# LiDAR_Lite_Interface.net
KiCad netlist of a schematic drawn in EAGLE
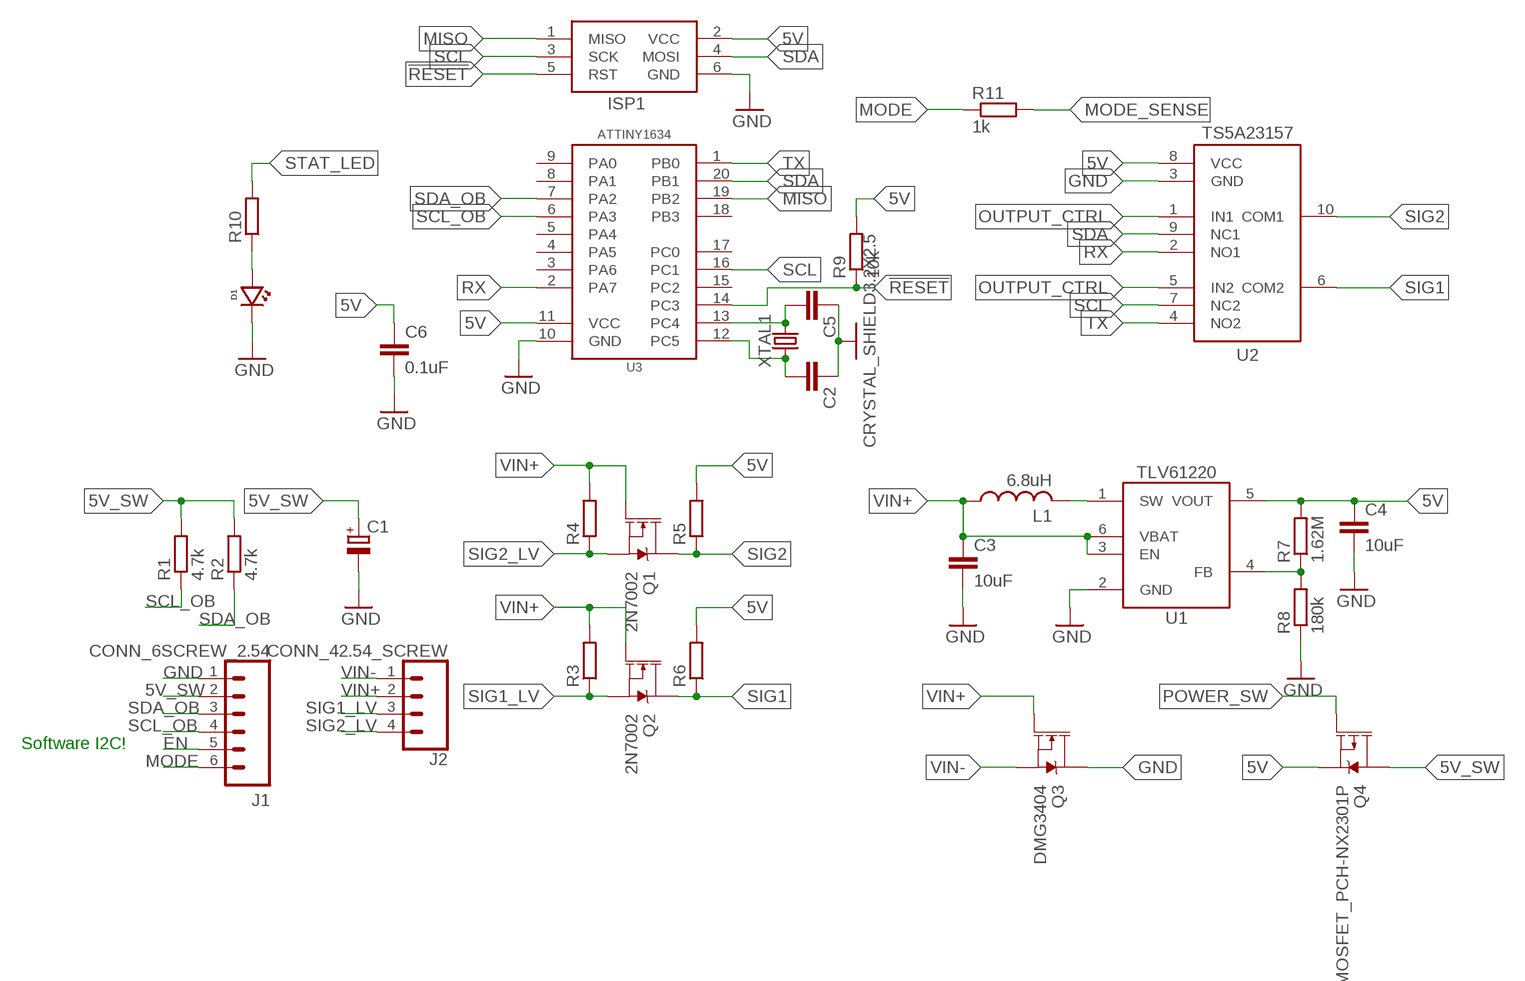
[diagram p0: schematic, sheet 1]

(export (version "E")
  (design (tool "Eeschema 10.0.6"))
  (components
    (comp (ref "C1")
      (value "CPOL-EUUW-10X10")
      (footprint "eagle-import:UW-10X10_NICHICON")
      (libsource (lib "eagle-import") (part "CPOL-EUUW-10X10"))
    )
    (comp (ref "C2")
      (value "C-EUC0402")
      (footprint "eagle-import:C0402")
      (libsource (lib "eagle-import") (part "C-EUC0402"))
    )
    (comp (ref "C3")
      (value "10uF")
      (footprint "eagle-import:C0805")
      (fields (field (name "MF") "Murata") (field (name "MPN") "GRM21BR61C106KE15K"))
      (libsource (lib "eagle-import") (part "C-EUC080510UF"))
    )
    (comp (ref "C4")
      (value "10uF")
      (footprint "eagle-import:C0805")
      (fields (field (name "MF") "Murata") (field (name "MPN") "GRM21BR61C106KE15K"))
      (libsource (lib "eagle-import") (part "C-EUC080510UF"))
    )
    (comp (ref "C5")
      (value "C-EUC0402")
      (footprint "eagle-import:C0402")
      (libsource (lib "eagle-import") (part "C-EUC0402"))
    )
    (comp (ref "C6")
      (value "0.1uF")
      (footprint "eagle-import:C0402")
      (fields (field (name "MF") "Murata") (field (name "MPN") "GCM155R71C104KA55D"))
      (libsource (lib "eagle-import") (part "C-EUC04020.1UF"))
    )
    (comp (ref "D1")
      (value "LEDBLUE0603")
      (footprint "eagle-import:LED_0603")
      (fields (field (name "MF") "Wurth") (field (name "MPN") "150060BS75000"))
      (libsource (lib "eagle-import") (part "LED0603BLUE"))
    )
    (comp (ref "ISP1")
      (value "AVRISP-6")
      (footprint "eagle-import:AVRISP")
      (libsource (lib "eagle-import") (part "AVRISP-6"))
    )
    (comp (ref "J1")
      (value "CONN_6SCREW_2.54")
      (footprint "eagle-import:1X06_SCREW")
      (fields (field (name "MF") "OnShore") (field (name "MPN") "OSTVN06A150"))
      (libsource (lib "eagle-import") (part "CONN_6SCREW_2.54"))
    )
    (comp (ref "J2")
      (value "CONN_42.54_SCREW")
      (footprint "eagle-import:1X04_SCREW")
      (fields (field (name "MF") "On Shore") (field (name "MPN") "OSTVN04A150"))
      (libsource (lib "eagle-import") (part "CONN_42.54_SCREW"))
    )
    (comp (ref "L1")
      (value "6.8uH")
      (footprint "eagle-import:1008")
      (fields (field (name "MF") "Wurth") (field (name "MPN") "74438323068"))
      (libsource (lib "eagle-import") (part "INDUCTOR1008"))
    )
    (comp (ref "Q1")
      (value "2N7002")
      (footprint "eagle-import:SOT23-3")
      (fields (field (name "MF") "Nexperia") (field (name "MPN") "2N7002P,215"))
      (libsource (lib "eagle-import") (part "MOSFET-NCH-2N7002P"))
    )
    (comp (ref "Q2")
      (value "2N7002")
      (footprint "eagle-import:SOT23-3")
      (fields (field (name "MF") "Nexperia") (field (name "MPN") "2N7002P,215"))
      (libsource (lib "eagle-import") (part "MOSFET-NCH-2N7002P"))
    )
    (comp (ref "Q3")
      (value "DMG3404")
      (footprint "eagle-import:SOT23-3")
      (fields (field (name "MF") "Diodes Incorporated") (field (name "MPN") "DMG3404L-7"))
      (libsource (lib "eagle-import") (part "MOSFET-NCH-DMG3404L"))
    )
    (comp (ref "Q4")
      (value "MOSFET_PCH-NX2301P")
      (footprint "eagle-import:SOT23-3")
      (fields (field (name "MF") "Nexperia") (field (name "MPN") "NX2301P,215"))
      (libsource (lib "eagle-import") (part "MOSFET_PCH-NX2301P"))
    )
    (comp (ref "R1")
      (value "4.7k")
      (footprint "eagle-import:R0402")
      (fields (field (name "MF") "Yageo") (field (name "MPN") "RC0402JR-074K7L"))
      (libsource (lib "eagle-import") (part "R-EU_R04024.7K"))
    )
    (comp (ref "R2")
      (value "4.7k")
      (footprint "eagle-import:R0402")
      (fields (field (name "MF") "Yageo") (field (name "MPN") "RC0402JR-074K7L"))
      (libsource (lib "eagle-import") (part "R-EU_R04024.7K"))
    )
    (comp (ref "R3")
      (value "R-EU_10KR0402")
      (footprint "eagle-import:R0402")
      (fields
        (field (name "MF") "Yageo")
        (field (name "MPN") "RC0603FR-0710KL")
        (field (name "VALUE_PART") "10k")
      )
      (libsource (lib "eagle-import") (part "R-EU_R040210K"))
    )
    (comp (ref "R4")
      (value "R-EU_10KR0402")
      (footprint "eagle-import:R0402")
      (fields
        (field (name "MF") "Yageo")
        (field (name "MPN") "RC0603FR-0710KL")
        (field (name "VALUE_PART") "10k")
      )
      (libsource (lib "eagle-import") (part "R-EU_R040210K"))
    )
    (comp (ref "R5")
      (value "R-EU_10KR0402")
      (footprint "eagle-import:R0402")
      (fields
        (field (name "MF") "Yageo")
        (field (name "MPN") "RC0603FR-0710KL")
        (field (name "VALUE_PART") "10k")
      )
      (libsource (lib "eagle-import") (part "R-EU_R040210K"))
    )
    (comp (ref "R6")
      (value "R-EU_10KR0402")
      (footprint "eagle-import:R0402")
      (fields
        (field (name "MF") "Yageo")
        (field (name "MPN") "RC0603FR-0710KL")
        (field (name "VALUE_PART") "10k")
      )
      (libsource (lib "eagle-import") (part "R-EU_R040210K"))
    )
    (comp (ref "R7")
      (value "1.62M")
      (footprint "eagle-import:R0603")
      (fields (field (name "MF") "Stackpole") (field (name "MPN") "RMCF0603FT1M62"))
      (libsource (lib "eagle-import") (part "R-EU_R06031.62M"))
    )
    (comp (ref "R8")
      (value "180k")
      (footprint "eagle-import:R0603")
      (fields (field (name "MF") "Panasonic") (field (name "MPN") "ERJ-3EKF1803V"))
      (libsource (lib "eagle-import") (part "R-EU_R0603180K"))
    )
    (comp (ref "R9")
      (value "10k")
      (footprint "eagle-import:R0402")
      (fields (field (name "MF") "Yageo") (field (name "MPN") "RC0603FR-0710KL"))
      (libsource (lib "eagle-import") (part "R-EU_R040210K"))
    )
    (comp (ref "R10")
      (value "R-EU_R0402")
      (footprint "eagle-import:R0402")
      (fields (field (name "MF") "Yageo"))
      (libsource (lib "eagle-import") (part "R-EU_R0402"))
    )
    (comp (ref "R11")
      (value "1k")
      (footprint "eagle-import:R0402")
      (fields (field (name "MF") "Yageo") (field (name "MPN") "RC0402FR-071KL"))
      (libsource (lib "eagle-import") (part "R-EU_R04021K"))
    )
    (comp (ref "U1")
      (value "TLV61220DBV")
      (footprint "eagle-import:DBV_R-PDSO-G6")
      (fields (field (name "MF") "TI") (field (name "MPN") "TLV61220DBVR"))
      (libsource (lib "eagle-import") (part "TLV61220DBV"))
    )
    (comp (ref "U2")
      (value "TS5A23157DGS")
      (footprint "eagle-import:DGS0010A")
      (fields (field (name "DISP") "TS5A23157") (field (name "MF") "TI") (field (name "MPN") "TS5A23157DGSR"))
      (libsource (lib "eagle-import") (part "TS5A23157DGS"))
    )
    (comp (ref "U3")
      (value "ATTINY1634SOIC")
      (footprint "eagle-import:SO-20DW")
      (fields (field (name "MF") "Atmel") (field (name "MPN") "ATTINY1634-SUR"))
      (libsource (lib "eagle-import") (part "ATTINY1634SOIC"))
    )
    (comp (ref "XTAL1")
      (value "CRYSTAL_SHIELD3.2X2.5")
      (footprint "eagle-import:CRYSTAL_3.2X2.5_4-SMD")
      (fields (field (name "MF") "Abricon") (field (name "MPN") "ABM8G-12.000MHZ-4Y-T3"))
      (libsource (lib "eagle-import") (part "CRYSTAL_SHIELD3.2X2.5"))
    )
  )
  (nets
    (net (code "1") (name "/EN") (class "Default")
      (node (ref "J1") (pin "5") (pinfunction "5_5") (pintype "passive"))
    )
    (net (code "2") (name "/~{RESET}") (class "Default")
      (node (ref "ISP1") (pin "5") (pinfunction "RST_5") (pintype "output"))
      (node (ref "R9") (pin "1") (pinfunction "1_1") (pintype "passive"))
      (node (ref "U3") (pin "14") (pinfunction "PC3_14") (pintype "bidirectional"))
    )
    (net (code "3") (name "5V") (class "Default")
      (node (ref "C4") (pin "1") (pinfunction "1_1") (pintype "passive"))
      (node (ref "C6") (pin "1") (pinfunction "1_1") (pintype "passive"))
      (node (ref "ISP1") (pin "2") (pinfunction "VCC_2") (pintype "power_in"))
      (node (ref "Q4") (pin "2") (pinfunction "S_2") (pintype "bidirectional"))
      (node (ref "R5") (pin "2") (pinfunction "2_2") (pintype "passive"))
      (node (ref "R6") (pin "2") (pinfunction "2_2") (pintype "passive"))
      (node (ref "R7") (pin "2") (pinfunction "2_2") (pintype "passive"))
      (node (ref "R9") (pin "2") (pinfunction "2_2") (pintype "passive"))
      (node (ref "U1") (pin "5") (pinfunction "VOUT_5") (pintype "power_in"))
      (node (ref "U2") (pin "8") (pinfunction "VCC_8") (pintype "power_in"))
      (node (ref "U3") (pin "11") (pinfunction "VCC_11") (pintype "power_in"))
    )
    (net (code "4") (name "5V_SW") (class "Default")
      (node (ref "C1") (pin "+") (pinfunction "+_+") (pintype "passive"))
      (node (ref "J1") (pin "2") (pinfunction "2_2") (pintype "passive"))
      (node (ref "Q4") (pin "3") (pinfunction "D_3") (pintype "bidirectional"))
      (node (ref "R1") (pin "2") (pinfunction "2_2") (pintype "passive"))
      (node (ref "R2") (pin "2") (pinfunction "2_2") (pintype "passive"))
    )
    (net (code "5") (name "GND") (class "Default")
      (node (ref "C1") (pin "-") (pinfunction "-_-") (pintype "passive"))
      (node (ref "C2") (pin "1") (pinfunction "1_1") (pintype "passive"))
      (node (ref "C3") (pin "2") (pinfunction "2_2") (pintype "passive"))
      (node (ref "C4") (pin "2") (pinfunction "2_2") (pintype "passive"))
      (node (ref "C5") (pin "1") (pinfunction "1_1") (pintype "passive"))
      (node (ref "C6") (pin "2") (pinfunction "2_2") (pintype "passive"))
      (node (ref "D1") (pin "CATHODE") (pinfunction "CATHODE_CATHODE") (pintype "power_in"))
      (node (ref "ISP1") (pin "6") (pinfunction "GND_6") (pintype "power_in"))
      (node (ref "J1") (pin "1") (pinfunction "1_1") (pintype "passive"))
      (node (ref "Q3") (pin "3") (pinfunction "D_3") (pintype "bidirectional"))
      (node (ref "R8") (pin "1") (pinfunction "1_1") (pintype "passive"))
      (node (ref "U1") (pin "2") (pinfunction "GND_2") (pintype "power_in"))
      (node (ref "U2") (pin "3") (pinfunction "GND_3") (pintype "power_in"))
      (node (ref "U3") (pin "10") (pinfunction "GND_10") (pintype "power_in"))
      (node (ref "XTAL1") (pin "2") (pinfunction "GND_2") (pintype "power_in"))
      (node (ref "XTAL1") (pin "4") (pinfunction "GND_4") (pintype "power_in"))
    )
    (net (code "6") (name "MISO") (class "Default")
      (node (ref "ISP1") (pin "1") (pinfunction "MISO_1") (pintype "input"))
      (node (ref "U3") (pin "19") (pinfunction "PB2_19") (pintype "bidirectional"))
    )
    (net (code "7") (name "MODE") (class "Default")
      (node (ref "J1") (pin "6") (pinfunction "6_6") (pintype "passive"))
      (node (ref "R11") (pin "1") (pinfunction "1_1") (pintype "passive"))
    )
    (net (code "8") (name "MODE_SENSE") (class "Default")
      (node (ref "R11") (pin "2") (pinfunction "2_2") (pintype "passive"))
    )
    (net (code "9") (name "Net-(D1-PadANODE)") (class "Default")
      (node (ref "D1") (pin "ANODE") (pinfunction "ANODE_ANODE") (pintype "power_in"))
      (node (ref "R10") (pin "1") (pinfunction "1_1") (pintype "passive"))
    )
    (net (code "10") (name "Net-(U1-FB)") (class "Default")
      (node (ref "R7") (pin "1") (pinfunction "1_1") (pintype "passive"))
      (node (ref "R8") (pin "2") (pinfunction "2_2") (pintype "passive"))
      (node (ref "U1") (pin "4") (pinfunction "FB_4") (pintype "input"))
    )
    (net (code "11") (name "Net-(U1-SW)") (class "Default")
      (node (ref "L1") (pin "2") (pinfunction "2_2") (pintype "passive"))
      (node (ref "U1") (pin "1") (pinfunction "SW_1") (pintype "power_in"))
    )
    (net (code "12") (name "Net-(U3-PC4)") (class "Default")
      (node (ref "C5") (pin "2") (pinfunction "2_2") (pintype "passive"))
      (node (ref "U3") (pin "13") (pinfunction "PC4_13") (pintype "bidirectional"))
      (node (ref "XTAL1") (pin "3") (pinfunction "2_3") (pintype "passive"))
    )
    (net (code "13") (name "Net-(U3-PC5)") (class "Default")
      (node (ref "C2") (pin "2") (pinfunction "2_2") (pintype "passive"))
      (node (ref "U3") (pin "12") (pinfunction "PC5_12") (pintype "bidirectional"))
      (node (ref "XTAL1") (pin "1") (pinfunction "1_1") (pintype "passive"))
    )
    (net (code "14") (name "OUTPUT_CTRL") (class "Default")
      (node (ref "U2") (pin "1") (pinfunction "IN1_1") (pintype "input"))
      (node (ref "U2") (pin "5") (pinfunction "IN2_5") (pintype "input"))
    )
    (net (code "15") (name "POWER_SW") (class "Default")
      (node (ref "Q4") (pin "1") (pinfunction "G_1") (pintype "bidirectional"))
    )
    (net (code "16") (name "RX") (class "Default")
      (node (ref "U2") (pin "2") (pinfunction "NO1_2") (pintype "bidirectional"))
      (node (ref "U3") (pin "2") (pinfunction "PA7_2") (pintype "bidirectional"))
    )
    (net (code "17") (name "SCL") (class "Default")
      (node (ref "ISP1") (pin "3") (pinfunction "SCK_3") (pintype "output"))
      (node (ref "U2") (pin "7") (pinfunction "NC2_7") (pintype "bidirectional"))
      (node (ref "U3") (pin "16") (pinfunction "PC1_16") (pintype "bidirectional"))
    )
    (net (code "18") (name "SCL_OB") (class "Default")
      (node (ref "J1") (pin "4") (pinfunction "4_4") (pintype "passive"))
      (node (ref "R1") (pin "1") (pinfunction "1_1") (pintype "passive"))
      (node (ref "U3") (pin "6") (pinfunction "PA3_6") (pintype "bidirectional"))
    )
    (net (code "19") (name "SDA") (class "Default")
      (node (ref "ISP1") (pin "4") (pinfunction "MOSI_4") (pintype "output"))
      (node (ref "U2") (pin "9") (pinfunction "NC1_9") (pintype "bidirectional"))
      (node (ref "U3") (pin "20") (pinfunction "PB1_20") (pintype "bidirectional"))
    )
    (net (code "20") (name "SDA_OB") (class "Default")
      (node (ref "J1") (pin "3") (pinfunction "3_3") (pintype "passive"))
      (node (ref "R2") (pin "1") (pinfunction "1_1") (pintype "passive"))
      (node (ref "U3") (pin "7") (pinfunction "PA2_7") (pintype "bidirectional"))
    )
    (net (code "21") (name "SIG1") (class "Default")
      (node (ref "Q2") (pin "3") (pinfunction "D_3") (pintype "bidirectional"))
      (node (ref "R6") (pin "1") (pinfunction "1_1") (pintype "passive"))
      (node (ref "U2") (pin "6") (pinfunction "COM2_6") (pintype "bidirectional"))
    )
    (net (code "22") (name "SIG1_LV") (class "Default")
      (node (ref "J2") (pin "3") (pinfunction "3_3") (pintype "passive"))
      (node (ref "Q2") (pin "2") (pinfunction "S_2") (pintype "bidirectional"))
      (node (ref "R3") (pin "1") (pinfunction "1_1") (pintype "passive"))
    )
    (net (code "23") (name "SIG2") (class "Default")
      (node (ref "Q1") (pin "3") (pinfunction "D_3") (pintype "bidirectional"))
      (node (ref "R5") (pin "1") (pinfunction "1_1") (pintype "passive"))
      (node (ref "U2") (pin "10") (pinfunction "COM1_10") (pintype "bidirectional"))
    )
    (net (code "24") (name "SIG2_LV") (class "Default")
      (node (ref "J2") (pin "4") (pinfunction "4_4") (pintype "passive"))
      (node (ref "Q1") (pin "2") (pinfunction "S_2") (pintype "bidirectional"))
      (node (ref "R4") (pin "1") (pinfunction "1_1") (pintype "passive"))
    )
    (net (code "25") (name "STAT_LED") (class "Default")
      (node (ref "R10") (pin "2") (pinfunction "2_2") (pintype "passive"))
    )
    (net (code "26") (name "TX") (class "Default")
      (node (ref "U2") (pin "4") (pinfunction "NO2_4") (pintype "bidirectional"))
      (node (ref "U3") (pin "1") (pinfunction "PB0_1") (pintype "bidirectional"))
    )
    (net (code "27") (name "VIN+") (class "Default")
      (node (ref "C3") (pin "1") (pinfunction "1_1") (pintype "passive"))
      (node (ref "J2") (pin "2") (pinfunction "2_2") (pintype "passive"))
      (node (ref "L1") (pin "1") (pinfunction "1_1") (pintype "passive"))
      (node (ref "Q1") (pin "1") (pinfunction "G_1") (pintype "bidirectional"))
      (node (ref "Q2") (pin "1") (pinfunction "G_1") (pintype "bidirectional"))
      (node (ref "Q3") (pin "1") (pinfunction "G_1") (pintype "bidirectional"))
      (node (ref "R3") (pin "2") (pinfunction "2_2") (pintype "passive"))
      (node (ref "R4") (pin "2") (pinfunction "2_2") (pintype "passive"))
      (node (ref "U1") (pin "3") (pinfunction "EN_3") (pintype "input"))
      (node (ref "U1") (pin "6") (pinfunction "VBAT_6") (pintype "power_in"))
    )
    (net (code "28") (name "VIN-") (class "Default")
      (node (ref "J2") (pin "1") (pinfunction "1_1") (pintype "passive"))
      (node (ref "Q3") (pin "2") (pinfunction "S_2") (pintype "bidirectional"))
    )
    (net (code "29") (name "unconnected-(U3-PA0-Pad9)") (class "Default")
      (node (ref "U3") (pin "9") (pinfunction "PA0_9") (pintype "bidirectional"))
    )
    (net (code "30") (name "unconnected-(U3-PA1-Pad8)") (class "Default")
      (node (ref "U3") (pin "8") (pinfunction "PA1_8") (pintype "bidirectional"))
    )
    (net (code "31") (name "unconnected-(U3-PA4-Pad5)") (class "Default")
      (node (ref "U3") (pin "5") (pinfunction "PA4_5") (pintype "bidirectional"))
    )
    (net (code "32") (name "unconnected-(U3-PA5-Pad4)") (class "Default")
      (node (ref "U3") (pin "4") (pinfunction "PA5_4") (pintype "bidirectional"))
    )
    (net (code "33") (name "unconnected-(U3-PA6-Pad3)") (class "Default")
      (node (ref "U3") (pin "3") (pinfunction "PA6_3") (pintype "bidirectional"))
    )
    (net (code "34") (name "unconnected-(U3-PB3-Pad18)") (class "Default")
      (node (ref "U3") (pin "18") (pinfunction "PB3_18") (pintype "bidirectional"))
    )
    (net (code "35") (name "unconnected-(U3-PC0-Pad17)") (class "Default")
      (node (ref "U3") (pin "17") (pinfunction "PC0_17") (pintype "bidirectional"))
    )
    (net (code "36") (name "unconnected-(U3-PC2-Pad15)") (class "Default")
      (node (ref "U3") (pin "15") (pinfunction "PC2_15") (pintype "bidirectional"))
    )
  )
)
